# OBDII-Ist.net
KiCad netlist of a schematic drawn in Altium Designer
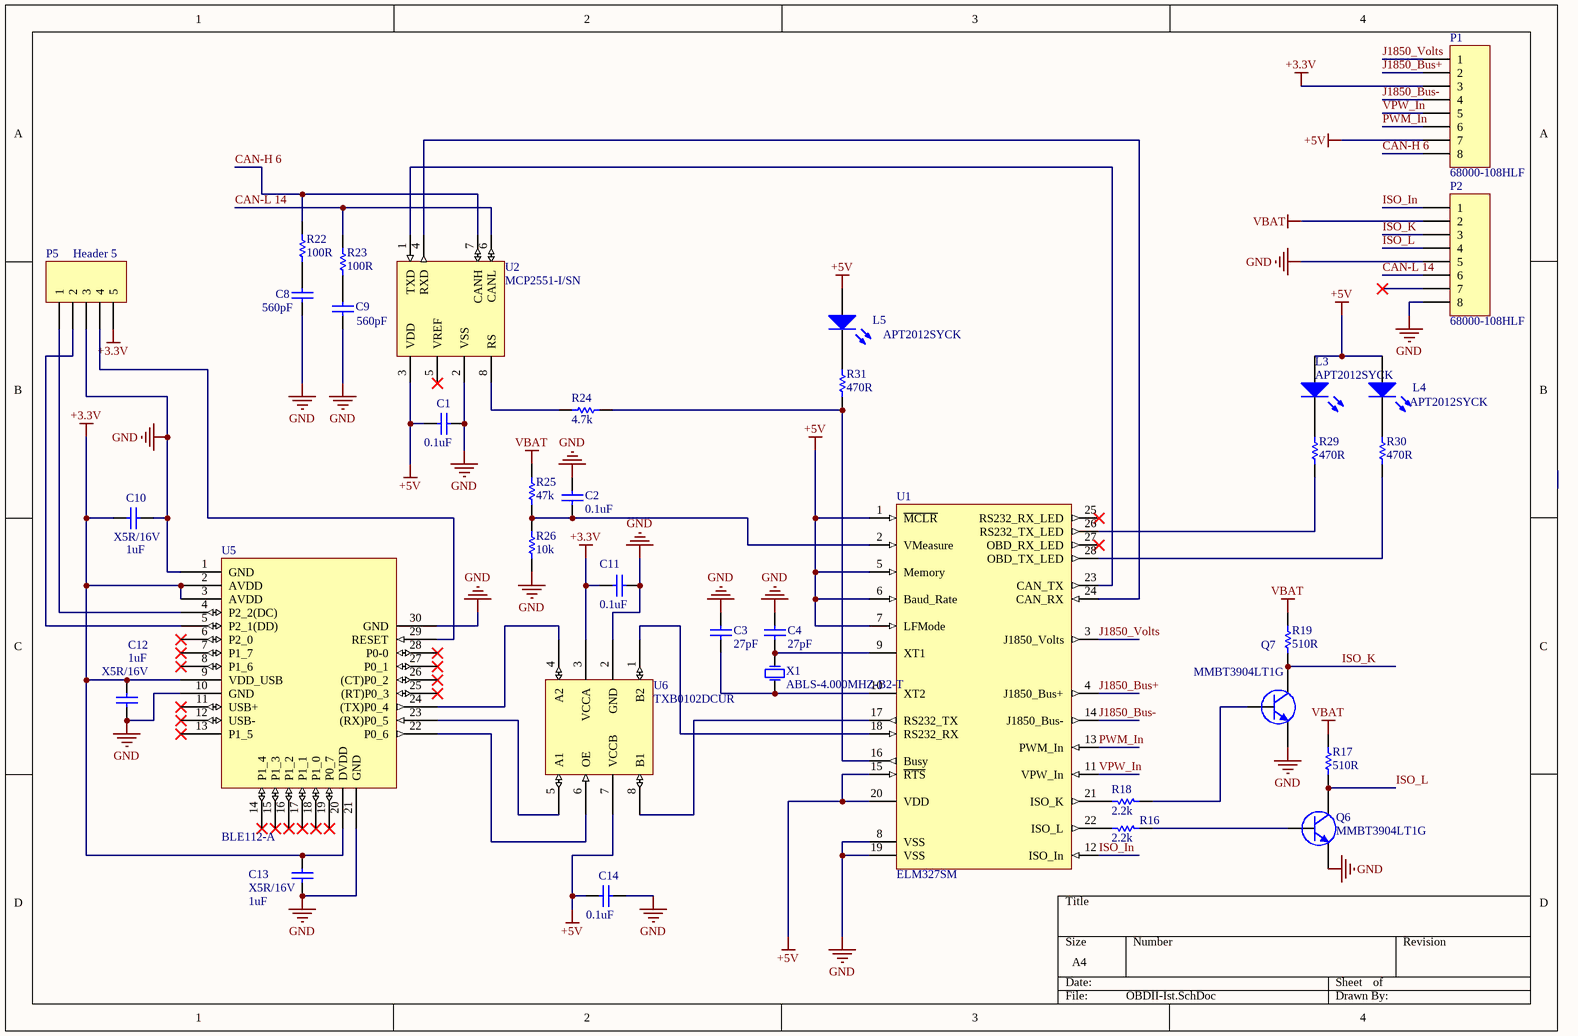
[diagram p0: OBDII-Ist.SchDoc]

(export (version "E")
  (design (tool "Eeschema 10.0.6"))
  (components
    (comp (ref "C1")
      (value "0.1uF")
      (footprint "1608[0603]")
      (description "Surface-Mount Ceramic Multilayer Capacitor, 0.1uF, X7R, 10% Tolerance, 0603 Size, 25V")
      (fields (field (name "PUBLISHER") "Altium Limited"))
      (libsource (lib "OBDII-components") (part "CGA3E2X7R1E104K080AA"))
    )
    (comp (ref "C2")
      (value "0.1uF")
      (footprint "1608[0603]")
      (description "Surface-Mount Ceramic Multilayer Capacitor, 0.1uF, X7R, 10% Tolerance, 0603 Size, 25V")
      (fields (field (name "PUBLISHER") "Altium Limited"))
      (libsource (lib "OBDII-components") (part "CGA3E2X7R1E104K080AA"))
    )
    (comp (ref "C3")
      (value "27pF")
      (footprint "1608[0603]")
      (description "Surface-Mount Ceramic Multilayer Capacitor, 27pF, 5% Tolerance, 0603 Size, 50V")
      (fields (field (name "PUBLISHER") "Altium Limited"))
      (libsource (lib "OBDII-components") (part "CC0603JRNPO9BN270"))
    )
    (comp (ref "C4")
      (value "27pF")
      (footprint "1608[0603]")
      (description "Surface-Mount Ceramic Multilayer Capacitor, 27pF, 5% Tolerance, 0603 Size, 50V")
      (fields (field (name "PUBLISHER") "Altium Limited"))
      (libsource (lib "OBDII-components") (part "CC0603JRNPO9BN270"))
    )
    (comp (ref "C8")
      (value "560pF")
      (footprint "0402")
      (description "Surface-Mount Ceramic Multilayer Capacitor, 560pF, 5% Tolerance, 0402 Size, 50V")
      (fields (field (name "PUBLISHER") "Altium Limited"))
      (libsource (lib "OBDII-components") (part "C0402C561J5GACTU"))
    )
    (comp (ref "C9")
      (value "560pF")
      (footprint "0402")
      (description "Surface-Mount Ceramic Multilayer Capacitor, 560pF, 5% Tolerance, 0402 Size, 50V")
      (fields (field (name "PUBLISHER") "Altium Limited"))
      (libsource (lib "OBDII-components") (part "C0402C561J5GACTU"))
    )
    (comp (ref "C10")
      (value "X5R/16V")
      (footprint "0402")
      (description "Capacitor (Semiconductor SIM Model)")
      (fields (field (name "ALTIUM_VALUE") "1uF") (field (name "PUBLISHER") "Altium Limited"))
      (libsource (lib "Miscellaneous Devices") (part "Cap Semi"))
    )
    (comp (ref "C11")
      (value "0.1uF")
      (footprint "1608[0603]")
      (description "Surface-Mount Ceramic Multilayer Capacitor, 0.1uF, X7R, 10% Tolerance, 0603 Size, 25V")
      (fields (field (name "PUBLISHER") "Altium Limited"))
      (libsource (lib "OBDII-components") (part "CGA3E2X7R1E104K080AA"))
    )
    (comp (ref "C12")
      (value "X5R/16V")
      (footprint "0402")
      (description "Capacitor (Semiconductor SIM Model)")
      (fields (field (name "ALTIUM_VALUE") "1uF") (field (name "PUBLISHER") "Altium Limited"))
      (libsource (lib "Miscellaneous Devices") (part "Cap Semi"))
    )
    (comp (ref "C13")
      (value "X5R/16V")
      (footprint "0402")
      (description "Capacitor (Semiconductor SIM Model)")
      (fields (field (name "ALTIUM_VALUE") "1uF") (field (name "PUBLISHER") "Altium Limited"))
      (libsource (lib "Miscellaneous Devices") (part "Cap Semi"))
    )
    (comp (ref "C14")
      (value "0.1uF")
      (footprint "1608[0603]")
      (description "Surface-Mount Ceramic Multilayer Capacitor, 0.1uF, X7R, 10% Tolerance, 0603 Size, 25V")
      (fields (field (name "PUBLISHER") "Altium Limited"))
      (libsource (lib "OBDII-components") (part "CGA3E2X7R1E104K080AA"))
    )
    (comp (ref "L3")
      (value "APT2012SYCK")
      (footprint "LED-0805")
      (description "Typical BLUE SiC LED")
      (libsource (lib "OBDII-components") (part "APT2012SYCK"))
    )
    (comp (ref "L4")
      (value "APT2012SYCK")
      (footprint "LED-0805")
      (description "Typical BLUE SiC LED")
      (libsource (lib "OBDII-components") (part "APT2012SYCK"))
    )
    (comp (ref "L5")
      (value "APT2012SYCK")
      (footprint "LED-0805")
      (description "Typical BLUE SiC LED")
      (libsource (lib "OBDII-components") (part "APT2012SYCK"))
    )
    (comp (ref "P1")
      (value "68000-108HLF")
      (footprint "HDR1X8")
      (description "Header, 8-Pin, 2.54 pitch, 1 row")
      (fields (field (name "PUBLISHER") "Altium Limited"))
      (libsource (lib "OBDII-components") (part "68000-108HLF"))
    )
    (comp (ref "P2")
      (value "68000-108HLF")
      (footprint "HDR1X8")
      (description "Header, 8-Pin, 2.54 pitch, 1 row")
      (fields (field (name "PUBLISHER") "Altium Limited"))
      (libsource (lib "OBDII-components") (part "68000-108HLF"))
    )
    (comp (ref "P5")
      (value "Header 5")
      (footprint "HDR1X5")
      (description "Header, 5-Pin")
      (fields (field (name "PUBLISHER") "Altium Limited"))
      (libsource (lib "OBDII-components") (part "Header 5"))
    )
    (comp (ref "Q6")
      (value "MMBT3904LT1G")
      (footprint "SOT23")
      (description "NPN 3904 General Purpose Amplifier")
      (fields
        (field (name "MANUFACTURER") "ON Semiconductor")
        (field (name "PUBLISHER") "Vanteon")
        (field (name "APPROVED") "Yes by Implemenation")
      )
      (libsource (lib "OBDII-components") (part "MMBT3904L"))
    )
    (comp (ref "Q7")
      (value "MMBT3904LT1G")
      (footprint "SOT23")
      (description "NPN 3904 General Purpose Amplifier")
      (fields
        (field (name "MANUFACTURER") "ON Semiconductor")
        (field (name "PUBLISHER") "Vanteon")
        (field (name "APPROVED") "Yes by Implemenation")
      )
      (libsource (lib "OBDII-components") (part "MMBT3904L"))
    )
    (comp (ref "R16")
      (value "2.2k")
      (footprint "ERA-0805")
      (description "Rectangular Thick Film Chip Resistor, 2.2 kOhm, 0.1% Tolerance, 0805 Size, 0.125 W")
      (libsource (lib "OBDII-components") (part "ERA6AEB222V"))
    )
    (comp (ref "R17")
      (value "510R")
      (footprint "ERJ-1210")
      (description "Rectangular Thick Film Chip Resistor, 510 Ohm, 1% Tolerance, 1210 Size, 0.5 W")
      (libsource (lib "OBDII-components") (part "ERJ14NF5100U"))
    )
    (comp (ref "R18")
      (value "2.2k")
      (footprint "ERA-0805")
      (description "Rectangular Thick Film Chip Resistor, 2.2 kOhm, 0.1% Tolerance, 0805 Size, 0.125 W")
      (libsource (lib "OBDII-components") (part "ERA6AEB222V"))
    )
    (comp (ref "R19")
      (value "510R")
      (footprint "ERJ-1210")
      (description "Rectangular Thick Film Chip Resistor, 510 Ohm, 1% Tolerance, 1210 Size, 0.5 W")
      (libsource (lib "OBDII-components") (part "ERJ14NF5100U"))
    )
    (comp (ref "R22")
      (value "100R")
      (footprint "ERA-0805")
      (description "Rectangular Thick Film Chip Resistor, 100 Ohm, 0.1% Tolerance, 0805 Size, 0.125 W")
      (libsource (lib "OBDII-components") (part "ERA6AEB101V"))
    )
    (comp (ref "R23")
      (value "100R")
      (footprint "ERA-0805")
      (description "Rectangular Thick Film Chip Resistor, 100 Ohm, 0.1% Tolerance, 0805 Size, 0.125 W")
      (libsource (lib "OBDII-components") (part "ERA6AEB101V"))
    )
    (comp (ref "R24")
      (value "4.7k")
      (footprint "ERA-0805")
      (description "Rectangular Thick Film Chip Resistor, 4.7 kOhm, 0.1% Tolerance, 0805 Size, 0.125 W")
      (libsource (lib "OBDII-components") (part "ERA6AEB472V"))
    )
    (comp (ref "R25")
      (value "47k")
      (footprint "ERA-0805")
      (description "Rectangular Thick Film Chip Resistor, 47 kOhm, 0.1% Tolerance, 0805 Size, 0.125 W")
      (libsource (lib "OBDII-components") (part "ERA6AEB473V"))
    )
    (comp (ref "R26")
      (value "10k")
      (footprint "ERA-0805")
      (description "Rectangular Thick Film Chip Resistor, 10 kOhm, 0.1% Tolerance, 0805 Size, 0.125 W")
      (libsource (lib "OBDII-components") (part "ERA6AEB103V"))
    )
    (comp (ref "R29")
      (value "470R")
      (footprint "ERA-0805")
      (description "Rectangular Thick Film Chip Resistor, 470 Ohm, 0.1% Tolerance, 0805 Size, 0.125 W")
      (libsource (lib "OBDII-components") (part "ERA6AEB471V"))
    )
    (comp (ref "R30")
      (value "470R")
      (footprint "ERA-0805")
      (description "Rectangular Thick Film Chip Resistor, 470 Ohm, 0.1% Tolerance, 0805 Size, 0.125 W")
      (libsource (lib "OBDII-components") (part "ERA6AEB471V"))
    )
    (comp (ref "R31")
      (value "470R")
      (footprint "ERA-0805")
      (description "Rectangular Thick Film Chip Resistor, 470 Ohm, 0.1% Tolerance, 0805 Size, 0.125 W")
      (libsource (lib "OBDII-components") (part "ERA6AEB471V"))
    )
    (comp (ref "U1")
      (value "ELM327SM")
      (footprint "SOIC127P1030X264-28N")
      (description "OBDII Interpreter IC")
      (fields (field (name "MANUFACTURER") "Elm Electronics"))
      (libsource (lib "OBDII-components") (part "ELM327_SOIC"))
    )
    (comp (ref "U2")
      (value "MCP2551-I/SN")
      (footprint "SOIC8N")
      (description "IC TRANSCEIVER CAN HI-SPD 8-SOIC")
      (fields (field (name "MANUFACTURER") "Microchip Technology"))
      (libsource (lib "OBDII-components") (part "MCP2551-I/SN"))
    )
    (comp (ref "U5")
      (value "BLE112-A")
      (footprint "BLE112-A - II")
      (description "BLE112 Bluetooth Smart Module")
      (libsource (lib "OBDII-components") (part "BLE112-A"))
    )
    (comp (ref "U6")
      (value "TXB0102DCUR")
      (footprint "TXB0102DCUR")
      (description "2-Bit Bidirectional Voltage-Level Translator with Auto Direction Sensing and +/-15-kV ESD Protect")
      (libsource (lib "OBDII-components") (part "TXB0102DCUR"))
    )
    (comp (ref "X1")
      (value "ABLS-4.000MHZ-B2-T")
      (footprint "HC-49/US")
      (description "CRYSTAL 4.000 MHZ 18PF SMD")
      (fields (field (name "MANUFACTURER") "Abracon"))
      (libsource (lib "OBDII-components") (part "ABLS-4.000MHZ-B2-T"))
    )
  )
  (nets
    (net (code "1") (name "+3.3V") (class "Default")
      (node (ref "C10") (pin "1") (pinfunction "1_1") (pintype "passive"))
      (node (ref "C11") (pin "1") (pinfunction "1_1") (pintype "passive"))
      (node (ref "C12") (pin "2") (pinfunction "2_2") (pintype "passive"))
      (node (ref "C13") (pin "2") (pinfunction "2_2") (pintype "passive"))
      (node (ref "P1") (pin "3") (pinfunction "3_3") (pintype "passive"))
      (node (ref "P5") (pin "5") (pinfunction "5_5") (pintype "passive"))
      (node (ref "U5") (pin "2") (pinfunction "AVDD_2") (pintype "power_in"))
      (node (ref "U5") (pin "20") (pinfunction "DVDD_20") (pintype "power_in"))
      (node (ref "U5") (pin "3") (pinfunction "AVDD_3") (pintype "power_in"))
      (node (ref "U5") (pin "9") (pinfunction "VDD_USB_9") (pintype "power_in"))
      (node (ref "U6") (pin "3") (pinfunction "VCCA_3") (pintype "power_in"))
    )
    (net (code "2") (name "+5V") (class "Default")
      (node (ref "C1") (pin "1") (pinfunction "1_1") (pintype "passive"))
      (node (ref "C14") (pin "1") (pinfunction "1_1") (pintype "passive"))
      (node (ref "L3") (pin "1") (pinfunction "A_1") (pintype "passive"))
      (node (ref "L4") (pin "1") (pinfunction "A_1") (pintype "passive"))
      (node (ref "L5") (pin "1") (pinfunction "A_1") (pintype "passive"))
      (node (ref "P1") (pin "7") (pinfunction "7_7") (pintype "passive"))
      (node (ref "U1") (pin "1") (pinfunction "~{MCLR}_1") (pintype "input"))
      (node (ref "U1") (pin "15") (pinfunction "~{RTS}_15") (pintype "input"))
      (node (ref "U1") (pin "20") (pinfunction "VDD_20") (pintype "power_in"))
      (node (ref "U1") (pin "5") (pinfunction "Memory_5") (pintype "input"))
      (node (ref "U1") (pin "6") (pinfunction "Baud_Rate_6") (pintype "input"))
      (node (ref "U1") (pin "7") (pinfunction "LFMode_7") (pintype "input"))
      (node (ref "U2") (pin "3") (pinfunction "VDD_3") (pintype "power_in"))
      (node (ref "U6") (pin "7") (pinfunction "VCCB_7") (pintype "power_in"))
    )
    (net (code "3") (name "/CAN-H 6") (class "Default")
      (node (ref "P1") (pin "8") (pinfunction "8_8") (pintype "passive"))
      (node (ref "R22") (pin "2") (pinfunction "2_2") (pintype "passive"))
      (node (ref "U2") (pin "7") (pinfunction "CANH_7") (pintype "bidirectional"))
    )
    (net (code "4") (name "/CAN-L 14") (class "Default")
      (node (ref "P2") (pin "6") (pinfunction "6_6") (pintype "passive"))
      (node (ref "R23") (pin "2") (pinfunction "2_2") (pintype "passive"))
      (node (ref "U2") (pin "6") (pinfunction "CANL_6") (pintype "bidirectional"))
    )
    (net (code "5") (name "/ISO_In") (class "Default")
      (node (ref "P2") (pin "1") (pinfunction "1_1") (pintype "passive"))
      (node (ref "U1") (pin "12") (pinfunction "ISO_In_12") (pintype "input"))
    )
    (net (code "6") (name "/ISO_K") (class "Default")
      (node (ref "P2") (pin "3") (pinfunction "3_3") (pintype "passive"))
      (node (ref "Q7") (pin "3") (pinfunction "C_3") (pintype "passive"))
      (node (ref "R19") (pin "1") (pinfunction "1_1") (pintype "passive"))
    )
    (net (code "7") (name "/ISO_L") (class "Default")
      (node (ref "P2") (pin "4") (pinfunction "4_4") (pintype "passive"))
      (node (ref "Q6") (pin "3") (pinfunction "C_3") (pintype "passive"))
      (node (ref "R17") (pin "1") (pinfunction "1_1") (pintype "passive"))
    )
    (net (code "8") (name "/J1850_Bus+") (class "Default")
      (node (ref "P1") (pin "2") (pinfunction "2_2") (pintype "passive"))
      (node (ref "U1") (pin "4") (pinfunction "J1850_Bus+_4") (pintype "output"))
    )
    (net (code "9") (name "/J1850_Bus-") (class "Default")
      (node (ref "P1") (pin "4") (pinfunction "4_4") (pintype "passive"))
      (node (ref "U1") (pin "14") (pinfunction "J1850_Bus-_14") (pintype "output"))
    )
    (net (code "10") (name "/J1850_Volts") (class "Default")
      (node (ref "P1") (pin "1") (pinfunction "1_1") (pintype "passive"))
      (node (ref "U1") (pin "3") (pinfunction "J1850_Volts_3") (pintype "output"))
    )
    (net (code "11") (name "/PWM_In") (class "Default")
      (node (ref "P1") (pin "6") (pinfunction "6_6") (pintype "passive"))
      (node (ref "U1") (pin "13") (pinfunction "PWM_In_13") (pintype "input"))
    )
    (net (code "12") (name "/VPW_In") (class "Default")
      (node (ref "P1") (pin "5") (pinfunction "5_5") (pintype "passive"))
      (node (ref "U1") (pin "11") (pinfunction "VPW_In_11") (pintype "input"))
    )
    (net (code "13") (name "GND") (class "Default")
      (node (ref "C1") (pin "2") (pinfunction "2_2") (pintype "passive"))
      (node (ref "C10") (pin "2") (pinfunction "2_2") (pintype "passive"))
      (node (ref "C11") (pin "2") (pinfunction "2_2") (pintype "passive"))
      (node (ref "C12") (pin "1") (pinfunction "1_1") (pintype "passive"))
      (node (ref "C13") (pin "1") (pinfunction "1_1") (pintype "passive"))
      (node (ref "C14") (pin "2") (pinfunction "2_2") (pintype "passive"))
      (node (ref "C2") (pin "2") (pinfunction "2_2") (pintype "passive"))
      (node (ref "C3") (pin "2") (pinfunction "2_2") (pintype "passive"))
      (node (ref "C4") (pin "2") (pinfunction "2_2") (pintype "passive"))
      (node (ref "C8") (pin "1") (pinfunction "1_1") (pintype "passive"))
      (node (ref "C9") (pin "1") (pinfunction "1_1") (pintype "passive"))
      (node (ref "P2") (pin "5") (pinfunction "5_5") (pintype "passive"))
      (node (ref "P2") (pin "8") (pinfunction "8_8") (pintype "passive"))
      (node (ref "P5") (pin "3") (pinfunction "3_3") (pintype "passive"))
      (node (ref "Q6") (pin "2") (pinfunction "E_2") (pintype "passive"))
      (node (ref "Q7") (pin "2") (pinfunction "E_2") (pintype "passive"))
      (node (ref "R26") (pin "1") (pinfunction "1_1") (pintype "passive"))
      (node (ref "U1") (pin "19") (pinfunction "VSS_19") (pintype "power_in"))
      (node (ref "U1") (pin "8") (pinfunction "VSS_8") (pintype "power_in"))
      (node (ref "U2") (pin "2") (pinfunction "VSS_2") (pintype "power_in"))
      (node (ref "U5") (pin "1") (pinfunction "GND_1") (pintype "power_in"))
      (node (ref "U5") (pin "10") (pinfunction "GND_10") (pintype "passive"))
      (node (ref "U5") (pin "21") (pinfunction "GND_21") (pintype "power_in"))
      (node (ref "U5") (pin "30") (pinfunction "GND_30") (pintype "power_in"))
      (node (ref "U6") (pin "2") (pinfunction "GND_2") (pintype "power_in"))
    )
    (net (code "14") (name "Net-(C8-Pad2)") (class "Default")
      (node (ref "C8") (pin "2") (pinfunction "2_2") (pintype "passive"))
      (node (ref "R22") (pin "1") (pinfunction "1_1") (pintype "passive"))
    )
    (net (code "15") (name "Net-(C9-Pad2)") (class "Default")
      (node (ref "C9") (pin "2") (pinfunction "2_2") (pintype "passive"))
      (node (ref "R23") (pin "1") (pinfunction "1_1") (pintype "passive"))
    )
    (net (code "16") (name "Net-(L3-K)") (class "Default")
      (node (ref "L3") (pin "2") (pinfunction "K_2") (pintype "passive"))
      (node (ref "R29") (pin "2") (pinfunction "2_2") (pintype "passive"))
    )
    (net (code "17") (name "Net-(L4-K)") (class "Default")
      (node (ref "L4") (pin "2") (pinfunction "K_2") (pintype "passive"))
      (node (ref "R30") (pin "2") (pinfunction "2_2") (pintype "passive"))
    )
    (net (code "18") (name "Net-(L5-K)") (class "Default")
      (node (ref "L5") (pin "2") (pinfunction "K_2") (pintype "passive"))
      (node (ref "R31") (pin "2") (pinfunction "2_2") (pintype "passive"))
    )
    (net (code "19") (name "Net-(Q6-B)") (class "Default")
      (node (ref "Q6") (pin "1") (pinfunction "B_1") (pintype "passive"))
      (node (ref "R16") (pin "1") (pinfunction "1_1") (pintype "passive"))
    )
    (net (code "20") (name "Net-(Q7-B)") (class "Default")
      (node (ref "Q7") (pin "1") (pinfunction "B_1") (pintype "passive"))
      (node (ref "R18") (pin "1") (pinfunction "1_1") (pintype "passive"))
    )
    (net (code "21") (name "Net-(U1-Busy)") (class "Default")
      (node (ref "R24") (pin "2") (pinfunction "2_2") (pintype "passive"))
      (node (ref "R31") (pin "1") (pinfunction "1_1") (pintype "passive"))
      (node (ref "U1") (pin "16") (pinfunction "Busy_16") (pintype "output"))
    )
    (net (code "22") (name "Net-(U1-CAN_RX)") (class "Default")
      (node (ref "U1") (pin "24") (pinfunction "CAN_RX_24") (pintype "input"))
      (node (ref "U2") (pin "4") (pinfunction "RXD_4") (pintype "output"))
    )
    (net (code "23") (name "Net-(U1-CAN_TX)") (class "Default")
      (node (ref "U1") (pin "23") (pinfunction "CAN_TX_23") (pintype "output"))
      (node (ref "U2") (pin "1") (pinfunction "TXD_1") (pintype "input"))
    )
    (net (code "24") (name "Net-(U1-ISO_K)") (class "Default")
      (node (ref "R18") (pin "2") (pinfunction "2_2") (pintype "passive"))
      (node (ref "U1") (pin "21") (pinfunction "ISO_K_21") (pintype "output"))
    )
    (net (code "25") (name "Net-(U1-ISO_L)") (class "Default")
      (node (ref "R16") (pin "2") (pinfunction "2_2") (pintype "passive"))
      (node (ref "U1") (pin "22") (pinfunction "ISO_L_22") (pintype "output"))
    )
    (net (code "26") (name "Net-(U1-OBD_TX_LED)") (class "Default")
      (node (ref "R30") (pin "1") (pinfunction "1_1") (pintype "passive"))
      (node (ref "U1") (pin "28") (pinfunction "OBD_TX_LED_28") (pintype "output"))
    )
    (net (code "27") (name "Net-(U1-RS232_RX)") (class "Default")
      (node (ref "U1") (pin "18") (pinfunction "RS232_RX_18") (pintype "input"))
      (node (ref "U6") (pin "1") (pinfunction "B2_1") (pintype "bidirectional"))
    )
    (net (code "28") (name "Net-(U1-RS232_TX)") (class "Default")
      (node (ref "U1") (pin "17") (pinfunction "RS232_TX_17") (pintype "output"))
      (node (ref "U6") (pin "8") (pinfunction "B1_8") (pintype "bidirectional"))
    )
    (net (code "29") (name "Net-(U1-RS232_TX_LED)") (class "Default")
      (node (ref "R29") (pin "1") (pinfunction "1_1") (pintype "passive"))
      (node (ref "U1") (pin "26") (pinfunction "RS232_TX_LED_26") (pintype "output"))
    )
    (net (code "30") (name "Net-(U1-VMeasure)") (class "Default")
      (node (ref "C2") (pin "1") (pinfunction "1_1") (pintype "passive"))
      (node (ref "R25") (pin "1") (pinfunction "1_1") (pintype "passive"))
      (node (ref "R26") (pin "2") (pinfunction "2_2") (pintype "passive"))
      (node (ref "U1") (pin "2") (pinfunction "VMeasure_2") (pintype "input"))
    )
    (net (code "31") (name "Net-(U1-XT1)") (class "Default")
      (node (ref "C4") (pin "1") (pinfunction "1_1") (pintype "passive"))
      (node (ref "U1") (pin "9") (pinfunction "XT1_9") (pintype "passive"))
      (node (ref "X1") (pin "2") (pinfunction "OSC2_2") (pintype "passive"))
    )
    (net (code "32") (name "Net-(U1-XT2)") (class "Default")
      (node (ref "C3") (pin "1") (pinfunction "1_1") (pintype "passive"))
      (node (ref "U1") (pin "10") (pinfunction "XT2_10") (pintype "passive"))
      (node (ref "X1") (pin "1") (pinfunction "OSC1_1") (pintype "passive"))
    )
    (net (code "33") (name "Net-(U2-RS)") (class "Default")
      (node (ref "R24") (pin "1") (pinfunction "1_1") (pintype "passive"))
      (node (ref "U2") (pin "8") (pinfunction "RS_8") (pintype "passive"))
    )
    (net (code "34") (name "Net-(U5-(RX)P0_5)") (class "Default")
      (node (ref "U5") (pin "23") (pinfunction "(RX)P0_5_23") (pintype "input"))
      (node (ref "U6") (pin "5") (pinfunction "A1_5") (pintype "bidirectional"))
    )
    (net (code "35") (name "Net-(U5-(TX)P0_4)") (class "Default")
      (node (ref "U5") (pin "24") (pinfunction "(TX)P0_4_24") (pintype "output"))
      (node (ref "U6") (pin "4") (pinfunction "A2_4") (pintype "bidirectional"))
    )
    (net (code "36") (name "Net-(U5-P0_6)") (class "Default")
      (node (ref "U5") (pin "22") (pinfunction "P0_6_22") (pintype "output"))
      (node (ref "U6") (pin "6") (pinfunction "OE_6") (pintype "input"))
    )
    (net (code "37") (name "Net-(U5-P2_1(DD))") (class "Default")
      (node (ref "P5") (pin "2") (pinfunction "2_2") (pintype "passive"))
      (node (ref "U5") (pin "5") (pinfunction "P2_1(DD)_5") (pintype "bidirectional"))
    )
    (net (code "38") (name "Net-(U5-P2_2(DC))") (class "Default")
      (node (ref "P5") (pin "1") (pinfunction "1_1") (pintype "passive"))
      (node (ref "U5") (pin "4") (pinfunction "P2_2(DC)_4") (pintype "bidirectional"))
    )
    (net (code "39") (name "Net-(U5-RESET)") (class "Default")
      (node (ref "P5") (pin "4") (pinfunction "4_4") (pintype "passive"))
      (node (ref "U5") (pin "29") (pinfunction "RESET_29") (pintype "input"))
    )
    (net (code "40") (name "VBAT") (class "Default")
      (node (ref "P2") (pin "2") (pinfunction "2_2") (pintype "passive"))
      (node (ref "R17") (pin "2") (pinfunction "2_2") (pintype "passive"))
      (node (ref "R19") (pin "2") (pinfunction "2_2") (pintype "passive"))
      (node (ref "R25") (pin "2") (pinfunction "2_2") (pintype "passive"))
    )
    (net (code "41") (name "unconnected-(P2-Pad7)") (class "Default")
      (node (ref "P2") (pin "7") (pinfunction "7_7") (pintype "passive+no_connect"))
    )
    (net (code "42") (name "unconnected-(U1-OBD_RX_LED-Pad27)") (class "Default")
      (node (ref "U1") (pin "27") (pinfunction "OBD_RX_LED_27") (pintype "output+no_connect"))
    )
    (net (code "43") (name "unconnected-(U1-RS232_RX_LED-Pad25)") (class "Default")
      (node (ref "U1") (pin "25") (pinfunction "RS232_RX_LED_25") (pintype "output+no_connect"))
    )
    (net (code "44") (name "unconnected-(U2-VREF-Pad5)") (class "Default")
      (node (ref "U2") (pin "5") (pinfunction "VREF_5") (pintype "passive+no_connect"))
    )
    (net (code "45") (name "unconnected-(U5-(CT)P0_2-Pad26)") (class "Default")
      (node (ref "U5") (pin "26") (pinfunction "(CT)P0_2_26") (pintype "bidirectional+no_connect"))
    )
    (net (code "46") (name "unconnected-(U5-(RT)P0_3-Pad25)") (class "Default")
      (node (ref "U5") (pin "25") (pinfunction "(RT)P0_3_25") (pintype "bidirectional+no_connect"))
    )
    (net (code "47") (name "unconnected-(U5-P0-0-Pad28)") (class "Default")
      (node (ref "U5") (pin "28") (pinfunction "P0-0_28") (pintype "bidirectional+no_connect"))
    )
    (net (code "48") (name "unconnected-(U5-P0_1-Pad27)") (class "Default")
      (node (ref "U5") (pin "27") (pinfunction "P0_1_27") (pintype "bidirectional+no_connect"))
    )
    (net (code "49") (name "unconnected-(U5-P0_7-Pad19)") (class "Default")
      (node (ref "U5") (pin "19") (pinfunction "P0_7_19") (pintype "bidirectional+no_connect"))
    )
    (net (code "50") (name "unconnected-(U5-P1_0-Pad18)") (class "Default")
      (node (ref "U5") (pin "18") (pinfunction "P1_0_18") (pintype "bidirectional+no_connect"))
    )
    (net (code "51") (name "unconnected-(U5-P1_1-Pad17)") (class "Default")
      (node (ref "U5") (pin "17") (pinfunction "P1_1_17") (pintype "bidirectional+no_connect"))
    )
    (net (code "52") (name "unconnected-(U5-P1_2-Pad16)") (class "Default")
      (node (ref "U5") (pin "16") (pinfunction "P1_2_16") (pintype "bidirectional+no_connect"))
    )
    (net (code "53") (name "unconnected-(U5-P1_3-Pad15)") (class "Default")
      (node (ref "U5") (pin "15") (pinfunction "P1_3_15") (pintype "bidirectional+no_connect"))
    )
    (net (code "54") (name "unconnected-(U5-P1_4-Pad14)") (class "Default")
      (node (ref "U5") (pin "14") (pinfunction "P1_4_14") (pintype "bidirectional+no_connect"))
    )
    (net (code "55") (name "unconnected-(U5-P1_5-Pad13)") (class "Default")
      (node (ref "U5") (pin "13") (pinfunction "P1_5_13") (pintype "passive+no_connect"))
    )
    (net (code "56") (name "unconnected-(U5-P1_6-Pad8)") (class "Default")
      (node (ref "U5") (pin "8") (pinfunction "P1_6_8") (pintype "bidirectional+no_connect"))
    )
    (net (code "57") (name "unconnected-(U5-P1_7-Pad7)") (class "Default")
      (node (ref "U5") (pin "7") (pinfunction "P1_7_7") (pintype "bidirectional+no_connect"))
    )
    (net (code "58") (name "unconnected-(U5-P2_0-Pad6)") (class "Default")
      (node (ref "U5") (pin "6") (pinfunction "P2_0_6") (pintype "bidirectional+no_connect"))
    )
    (net (code "59") (name "unconnected-(U5-USB+-Pad11)") (class "Default")
      (node (ref "U5") (pin "11") (pinfunction "USB+_11") (pintype "bidirectional+no_connect"))
    )
    (net (code "60") (name "unconnected-(U5-USB--Pad12)") (class "Default")
      (node (ref "U5") (pin "12") (pinfunction "USB-_12") (pintype "bidirectional+no_connect"))
    )
  )
)
